# rpi-can-rs485.net
KiCad netlist of a schematic drawn in EAGLE
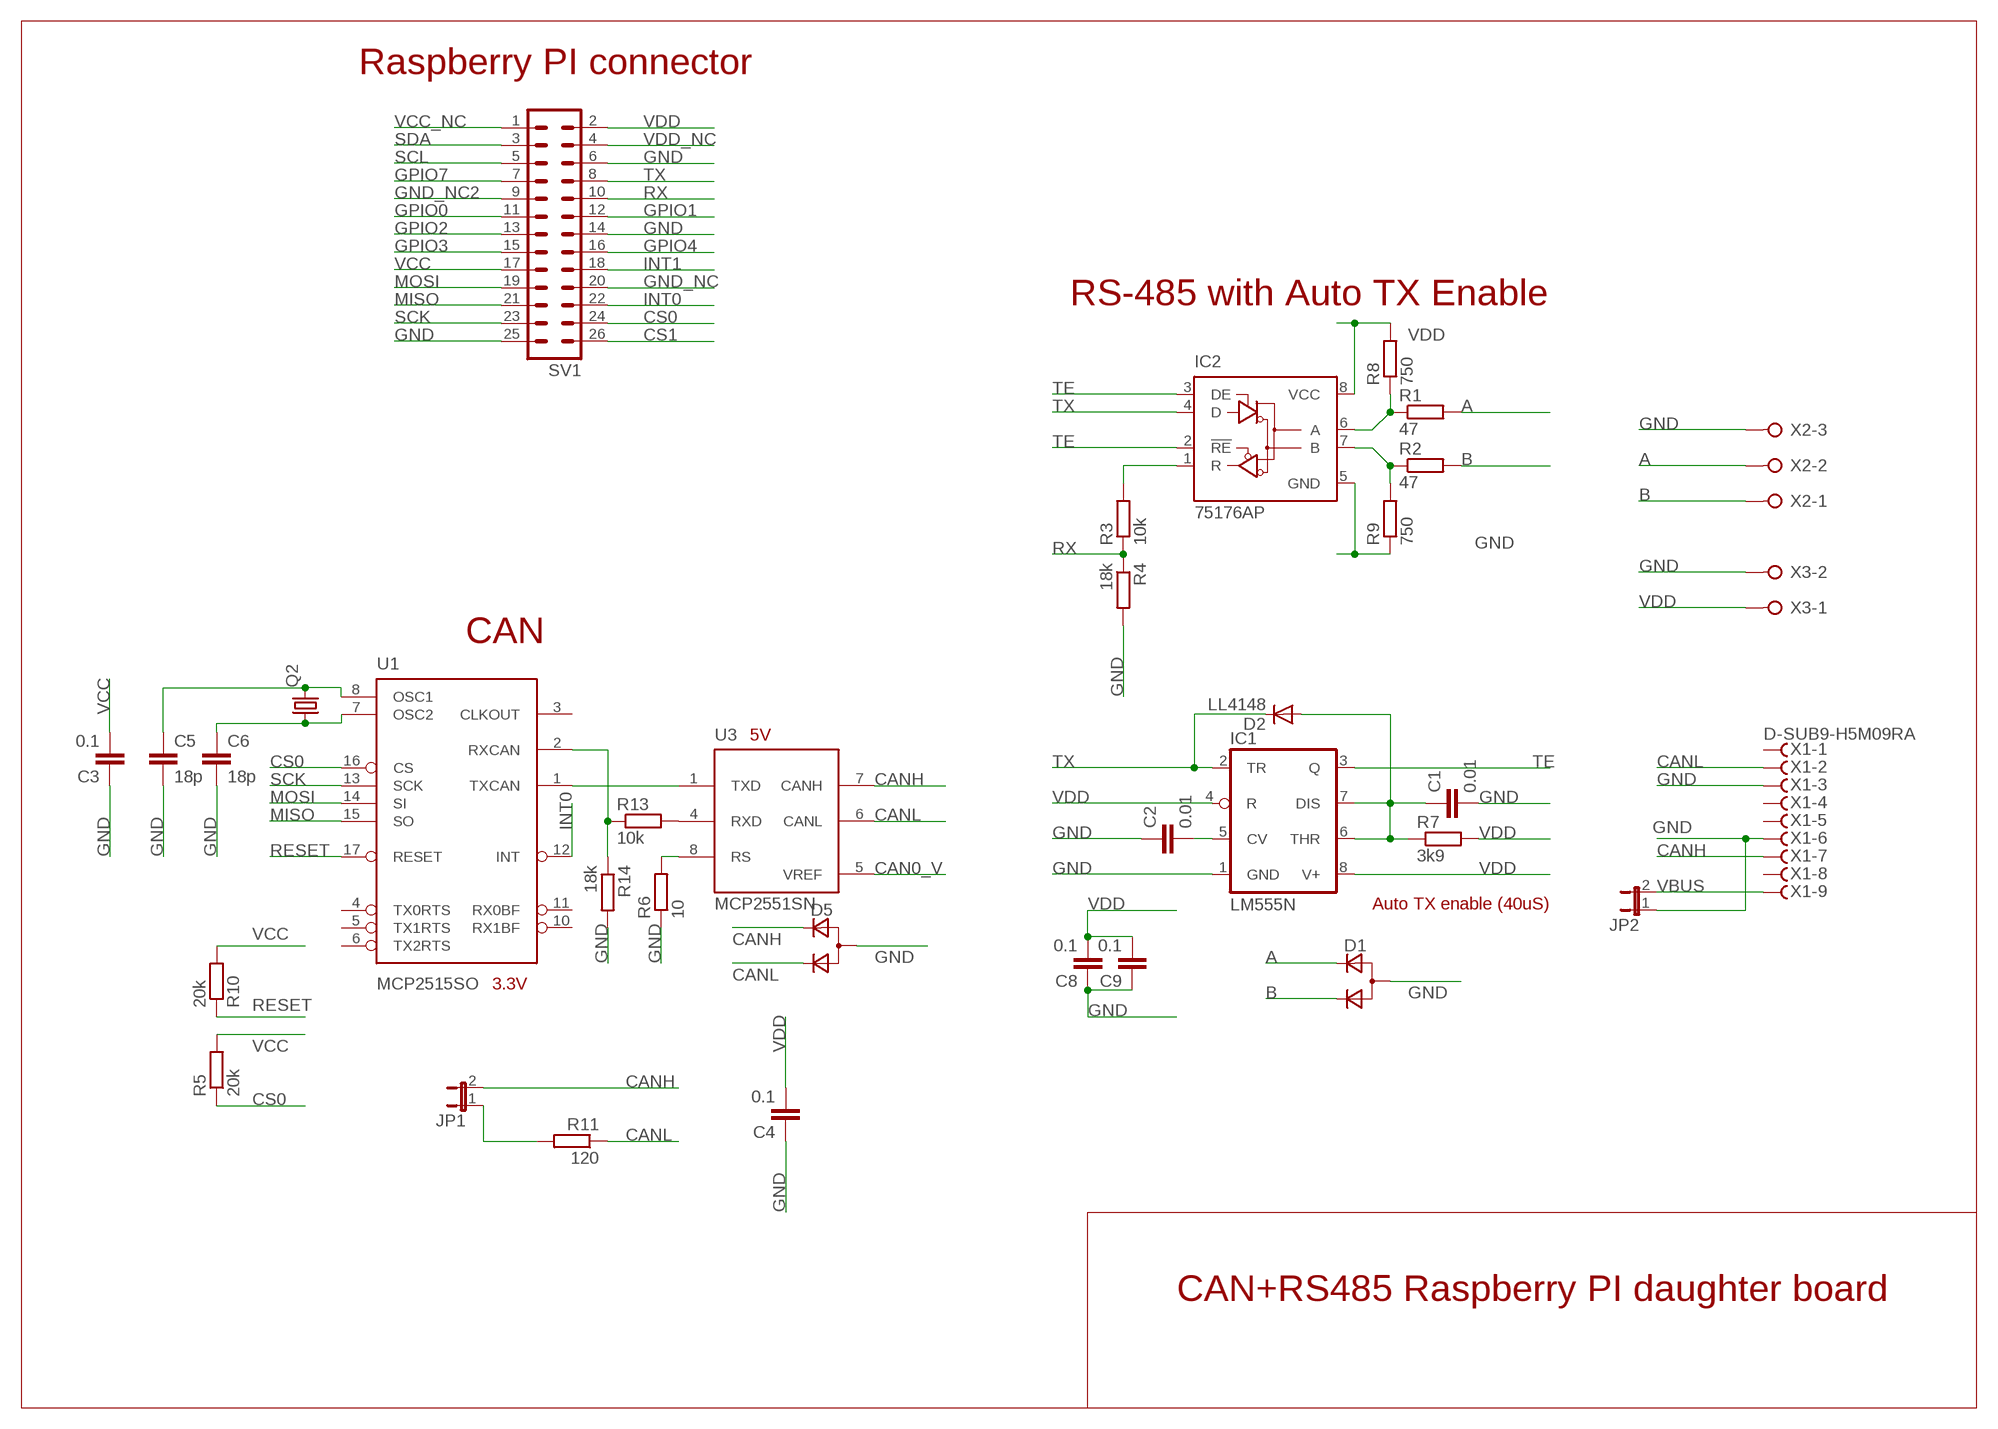
[diagram p0: schematic, sheet 1]

(export (version "E")
  (design (tool "Eeschema 10.0.6"))
  (components
    (comp (ref "C1")
      (value "0.01")
      (footprint "eagle-import:C0805")
      (libsource (lib "eagle-import") (part "C-EUC0805"))
    )
    (comp (ref "C2")
      (value "0.01")
      (footprint "eagle-import:C0805")
      (libsource (lib "eagle-import") (part "C-EUC0805"))
    )
    (comp (ref "C3")
      (value "0.1")
      (footprint "eagle-import:C0805")
      (libsource (lib "eagle-import") (part "C-EUC0805"))
    )
    (comp (ref "C4")
      (value "0.1")
      (footprint "eagle-import:C0805")
      (libsource (lib "eagle-import") (part "C-EUC0805"))
    )
    (comp (ref "C5")
      (value "18p")
      (footprint "eagle-import:C0805")
      (libsource (lib "eagle-import") (part "C-EUC0805"))
    )
    (comp (ref "C6")
      (value "18p")
      (footprint "eagle-import:C0805")
      (libsource (lib "eagle-import") (part "C-EUC0805"))
    )
    (comp (ref "C8")
      (value "0.1")
      (footprint "eagle-import:C0805")
      (libsource (lib "eagle-import") (part "C-EUC0805"))
    )
    (comp (ref "C9")
      (value "0.1")
      (footprint "eagle-import:C0805")
      (libsource (lib "eagle-import") (part "C-EUC0805"))
    )
    (comp (ref "D1")
      (value "D_2CSOT323")
      (footprint "eagle-import:SOT323")
      (libsource (lib "eagle-import") (part "D_2CSOT323"))
    )
    (comp (ref "D2")
      (value "LL4148")
      (footprint "eagle-import:SOD80C")
      (libsource (lib "eagle-import") (part "DIODE-SOD80C"))
    )
    (comp (ref "D5")
      (value "D_2CSOT323")
      (footprint "eagle-import:SOT323")
      (libsource (lib "eagle-import") (part "D_2CSOT323"))
    )
    (comp (ref "IC1")
      (value "LM555N")
      (footprint "eagle-import:DIL08")
      (libsource (lib "eagle-import") (part "555NLM"))
    )
    (comp (ref "IC2")
      (value "75176AP")
      (footprint "eagle-import:DIL08")
      (libsource (lib "eagle-import") (part "75176AP"))
    )
    (comp (ref "JP1")
      (value "JP1E")
      (footprint "eagle-import:JP1")
      (libsource (lib "eagle-import") (part "JP1E"))
    )
    (comp (ref "JP2")
      (value "JP1E")
      (footprint "eagle-import:JP1")
      (libsource (lib "eagle-import") (part "JP1E"))
    )
    (comp (ref "Q2")
      (value "CRYSTALHC49S")
      (footprint "eagle-import:HC49_S")
      (libsource (lib "eagle-import") (part "CRYSTALHC49S"))
    )
    (comp (ref "R1")
      (value "47")
      (footprint "eagle-import:R1206")
      (libsource (lib "eagle-import") (part "R-EU_R1206"))
    )
    (comp (ref "R2")
      (value "47")
      (footprint "eagle-import:R1206")
      (libsource (lib "eagle-import") (part "R-EU_R1206"))
    )
    (comp (ref "R3")
      (value "10k")
      (footprint "eagle-import:R0805")
      (libsource (lib "eagle-import") (part "R-EU_R0805"))
    )
    (comp (ref "R4")
      (value "18k")
      (footprint "eagle-import:R0805")
      (libsource (lib "eagle-import") (part "R-EU_R0805"))
    )
    (comp (ref "R5")
      (value "20k")
      (footprint "eagle-import:R0603")
      (libsource (lib "eagle-import") (part "R-EU_R0603"))
    )
    (comp (ref "R6")
      (value "10")
      (footprint "eagle-import:R0805")
      (libsource (lib "eagle-import") (part "R-EU_R0805"))
    )
    (comp (ref "R7")
      (value "3k9")
      (footprint "eagle-import:R0805")
      (libsource (lib "eagle-import") (part "R-EU_R0805"))
    )
    (comp (ref "R8")
      (value "750")
      (footprint "eagle-import:R1206")
      (libsource (lib "eagle-import") (part "R-EU_R1206"))
    )
    (comp (ref "R9")
      (value "750")
      (footprint "eagle-import:R1206")
      (libsource (lib "eagle-import") (part "R-EU_R1206"))
    )
    (comp (ref "R10")
      (value "20k")
      (footprint "eagle-import:R0805")
      (libsource (lib "eagle-import") (part "R-EU_R0805"))
    )
    (comp (ref "R11")
      (value "120")
      (footprint "eagle-import:R0805")
      (libsource (lib "eagle-import") (part "R-EU_R0805"))
    )
    (comp (ref "R13")
      (value "10k")
      (footprint "eagle-import:R0805")
      (libsource (lib "eagle-import") (part "R-EU_R0805"))
    )
    (comp (ref "R14")
      (value "18k")
      (footprint "eagle-import:R0805")
      (libsource (lib "eagle-import") (part "R-EU_R0805"))
    )
    (comp (ref "SV1")
      (value "MA13-2")
      (footprint "eagle-import:MA13-2")
      (libsource (lib "eagle-import") (part "MA13-2"))
    )
    (comp (ref "U1")
      (value "MCP2515SO")
      (footprint "eagle-import:SO-18W")
      (libsource (lib "eagle-import") (part "MCP2510SO"))
    )
    (comp (ref "U3")
      (value "MCP2551SN")
      (footprint "eagle-import:SO-08")
      (libsource (lib "eagle-import") (part "MCP2551SN"))
    )
    (comp (ref "X1")
      (value "D-SUB9-H5M09RA")
      (footprint "eagle-import:H5M09RA")
      (libsource (lib "eagle-import") (part "D-SUB9-H5M09RA"))
    )
    (comp (ref "X2")
      (value "W237-03P")
      (footprint "eagle-import:W237-133")
      (libsource (lib "eagle-import") (part "W237-03P"))
    )
    (comp (ref "X3")
      (value "W237-02P")
      (footprint "eagle-import:W237-132")
      (libsource (lib "eagle-import") (part "W237-02P"))
    )
  )
  (nets
    (net (code "1") (name "/A") (class "Default")
      (node (ref "D1") (pin "2") (pinfunction "C1_2") (pintype "passive"))
      (node (ref "R1") (pin "2") (pinfunction "2_2") (pintype "passive"))
      (node (ref "X2") (pin "2") (pinfunction "KL_2") (pintype "passive"))
    )
    (net (code "2") (name "/B") (class "Default")
      (node (ref "D1") (pin "3") (pinfunction "C2_3") (pintype "passive"))
      (node (ref "R2") (pin "2") (pinfunction "2_2") (pintype "passive"))
      (node (ref "X2") (pin "1") (pinfunction "KL_1") (pintype "passive"))
    )
    (net (code "3") (name "/CAN0_V") (class "Default")
      (node (ref "U3") (pin "5") (pinfunction "VREF_5") (pintype "power_in"))
    )
    (net (code "4") (name "/CANH") (class "Default")
      (node (ref "D5") (pin "2") (pinfunction "C1_2") (pintype "passive"))
      (node (ref "JP1") (pin "2") (pinfunction "2_2") (pintype "passive"))
      (node (ref "U3") (pin "7") (pinfunction "CANH_7") (pintype "bidirectional"))
      (node (ref "X1") (pin "7") (pinfunction "F_7") (pintype "passive"))
    )
    (net (code "5") (name "/CANL") (class "Default")
      (node (ref "D5") (pin "3") (pinfunction "C2_3") (pintype "passive"))
      (node (ref "R11") (pin "1") (pinfunction "1_1") (pintype "passive"))
      (node (ref "U3") (pin "6") (pinfunction "CANL_6") (pintype "bidirectional"))
      (node (ref "X1") (pin "2") (pinfunction "F_2") (pintype "passive"))
    )
    (net (code "6") (name "/CS0") (class "Default")
      (node (ref "R5") (pin "1") (pinfunction "1_1") (pintype "passive"))
      (node (ref "SV1") (pin "24") (pinfunction "24_24") (pintype "passive"))
      (node (ref "U1") (pin "16") (pinfunction "CS_16") (pintype "input"))
    )
    (net (code "7") (name "/CS1") (class "Default")
      (node (ref "SV1") (pin "26") (pinfunction "26_26") (pintype "passive"))
    )
    (net (code "8") (name "/GND") (class "Default")
      (node (ref "C1") (pin "2") (pinfunction "2_2") (pintype "passive"))
      (node (ref "C2") (pin "1") (pinfunction "1_1") (pintype "passive"))
      (node (ref "C3") (pin "1") (pinfunction "1_1") (pintype "passive"))
      (node (ref "C4") (pin "1") (pinfunction "1_1") (pintype "passive"))
      (node (ref "C5") (pin "2") (pinfunction "2_2") (pintype "passive"))
      (node (ref "C6") (pin "2") (pinfunction "2_2") (pintype "passive"))
      (node (ref "C8") (pin "1") (pinfunction "1_1") (pintype "passive"))
      (node (ref "C9") (pin "1") (pinfunction "1_1") (pintype "passive"))
      (node (ref "D1") (pin "1") (pinfunction "A_1") (pintype "passive"))
      (node (ref "D5") (pin "1") (pinfunction "A_1") (pintype "passive"))
      (node (ref "IC1") (pin "1") (pinfunction "GND_1") (pintype "power_in"))
      (node (ref "IC2") (pin "5") (pinfunction "GND_5") (pintype "power_in"))
      (node (ref "JP2") (pin "1") (pinfunction "1_1") (pintype "passive"))
      (node (ref "R14") (pin "2") (pinfunction "2_2") (pintype "passive"))
      (node (ref "R4") (pin "2") (pinfunction "2_2") (pintype "passive"))
      (node (ref "R6") (pin "1") (pinfunction "1_1") (pintype "passive"))
      (node (ref "R9") (pin "1") (pinfunction "1_1") (pintype "passive"))
      (node (ref "SV1") (pin "14") (pinfunction "14_14") (pintype "passive"))
      (node (ref "SV1") (pin "25") (pinfunction "25_25") (pintype "passive"))
      (node (ref "SV1") (pin "6") (pinfunction "6_6") (pintype "passive"))
      (node (ref "X1") (pin "3") (pinfunction "F_3") (pintype "passive"))
      (node (ref "X1") (pin "6") (pinfunction "F_6") (pintype "passive"))
      (node (ref "X2") (pin "3") (pinfunction "KL_3") (pintype "passive"))
      (node (ref "X3") (pin "2") (pinfunction "KL_2") (pintype "passive"))
    )
    (net (code "9") (name "/GND_NC") (class "Default")
      (node (ref "SV1") (pin "20") (pinfunction "20_20") (pintype "passive"))
    )
    (net (code "10") (name "/GND_NC2") (class "Default")
      (node (ref "SV1") (pin "9") (pinfunction "9_9") (pintype "passive"))
    )
    (net (code "11") (name "/GPIO0") (class "Default")
      (node (ref "SV1") (pin "11") (pinfunction "11_11") (pintype "passive"))
    )
    (net (code "12") (name "/GPIO1") (class "Default")
      (node (ref "SV1") (pin "12") (pinfunction "12_12") (pintype "passive"))
    )
    (net (code "13") (name "/GPIO2") (class "Default")
      (node (ref "SV1") (pin "13") (pinfunction "13_13") (pintype "passive"))
    )
    (net (code "14") (name "/GPIO3") (class "Default")
      (node (ref "SV1") (pin "15") (pinfunction "15_15") (pintype "passive"))
    )
    (net (code "15") (name "/GPIO4") (class "Default")
      (node (ref "SV1") (pin "16") (pinfunction "16_16") (pintype "passive"))
    )
    (net (code "16") (name "/GPIO7") (class "Default")
      (node (ref "SV1") (pin "7") (pinfunction "7_7") (pintype "passive"))
    )
    (net (code "17") (name "/INT0") (class "Default")
      (node (ref "SV1") (pin "22") (pinfunction "22_22") (pintype "passive"))
      (node (ref "U1") (pin "12") (pinfunction "INT_12") (pintype "output"))
    )
    (net (code "18") (name "/INT1") (class "Default")
      (node (ref "SV1") (pin "18") (pinfunction "18_18") (pintype "passive"))
    )
    (net (code "19") (name "/MISO") (class "Default")
      (node (ref "SV1") (pin "21") (pinfunction "21_21") (pintype "passive"))
      (node (ref "U1") (pin "15") (pinfunction "SO_15") (pintype "output"))
    )
    (net (code "20") (name "/MOSI") (class "Default")
      (node (ref "SV1") (pin "19") (pinfunction "19_19") (pintype "passive"))
      (node (ref "U1") (pin "14") (pinfunction "SI_14") (pintype "input"))
    )
    (net (code "21") (name "/RESET") (class "Default")
      (node (ref "R10") (pin "1") (pinfunction "1_1") (pintype "passive"))
      (node (ref "U1") (pin "17") (pinfunction "RESET_17") (pintype "input"))
    )
    (net (code "22") (name "/RX") (class "Default")
      (node (ref "R3") (pin "1") (pinfunction "1_1") (pintype "passive"))
      (node (ref "R4") (pin "1") (pinfunction "1_1") (pintype "passive"))
      (node (ref "SV1") (pin "10") (pinfunction "10_10") (pintype "passive"))
    )
    (net (code "23") (name "/SCK") (class "Default")
      (node (ref "SV1") (pin "23") (pinfunction "23_23") (pintype "passive"))
      (node (ref "U1") (pin "13") (pinfunction "SCK_13") (pintype "input"))
    )
    (net (code "24") (name "/SCL") (class "Default")
      (node (ref "SV1") (pin "5") (pinfunction "5_5") (pintype "passive"))
    )
    (net (code "25") (name "/SDA") (class "Default")
      (node (ref "SV1") (pin "3") (pinfunction "3_3") (pintype "passive"))
    )
    (net (code "26") (name "/TE") (class "Default")
      (node (ref "IC1") (pin "3") (pinfunction "Q_3") (pintype "output"))
      (node (ref "IC2") (pin "2") (pinfunction "~{RE}_2") (pintype "input"))
      (node (ref "IC2") (pin "3") (pinfunction "DE_3") (pintype "input"))
    )
    (net (code "27") (name "/TX") (class "Default")
      (node (ref "D2") (pin "C") (pinfunction "C_C") (pintype "passive"))
      (node (ref "IC1") (pin "2") (pinfunction "TR_2") (pintype "input"))
      (node (ref "IC2") (pin "4") (pinfunction "D_4") (pintype "input"))
      (node (ref "SV1") (pin "8") (pinfunction "8_8") (pintype "passive"))
    )
    (net (code "28") (name "/VBUS") (class "Default")
      (node (ref "JP2") (pin "2") (pinfunction "2_2") (pintype "passive"))
      (node (ref "X1") (pin "9") (pinfunction "F_9") (pintype "passive"))
    )
    (net (code "29") (name "/VCC") (class "Default")
      (node (ref "C3") (pin "2") (pinfunction "2_2") (pintype "passive"))
      (node (ref "R10") (pin "2") (pinfunction "2_2") (pintype "passive"))
      (node (ref "R5") (pin "2") (pinfunction "2_2") (pintype "passive"))
      (node (ref "SV1") (pin "17") (pinfunction "17_17") (pintype "passive"))
    )
    (net (code "30") (name "/VCC_NC") (class "Default")
      (node (ref "SV1") (pin "1") (pinfunction "1_1") (pintype "passive"))
    )
    (net (code "31") (name "/VDD") (class "Default")
      (node (ref "C4") (pin "2") (pinfunction "2_2") (pintype "passive"))
      (node (ref "C8") (pin "2") (pinfunction "2_2") (pintype "passive"))
      (node (ref "C9") (pin "2") (pinfunction "2_2") (pintype "passive"))
      (node (ref "IC1") (pin "4") (pinfunction "R_4") (pintype "input"))
      (node (ref "IC1") (pin "8") (pinfunction "V+_8") (pintype "power_in"))
      (node (ref "IC2") (pin "8") (pinfunction "VCC_8") (pintype "power_in"))
      (node (ref "R7") (pin "2") (pinfunction "2_2") (pintype "passive"))
      (node (ref "R8") (pin "2") (pinfunction "2_2") (pintype "passive"))
      (node (ref "SV1") (pin "2") (pinfunction "2_2") (pintype "passive"))
      (node (ref "X3") (pin "1") (pinfunction "KL_1") (pintype "passive"))
    )
    (net (code "32") (name "/VDD_NC") (class "Default")
      (node (ref "SV1") (pin "4") (pinfunction "4_4") (pintype "passive"))
    )
    (net (code "33") (name "Net-(IC1-CV)") (class "Default")
      (node (ref "C2") (pin "2") (pinfunction "2_2") (pintype "passive"))
      (node (ref "IC1") (pin "5") (pinfunction "CV_5") (pintype "input"))
    )
    (net (code "34") (name "Net-(IC1-DIS)") (class "Default")
      (node (ref "C1") (pin "1") (pinfunction "1_1") (pintype "passive"))
      (node (ref "D2") (pin "A") (pinfunction "A_A") (pintype "passive"))
      (node (ref "IC1") (pin "6") (pinfunction "THR_6") (pintype "input"))
      (node (ref "IC1") (pin "7") (pinfunction "DIS_7") (pintype "input"))
      (node (ref "R7") (pin "1") (pinfunction "1_1") (pintype "passive"))
    )
    (net (code "35") (name "Net-(IC2-A)") (class "Default")
      (node (ref "IC2") (pin "6") (pinfunction "A_6") (pintype "output"))
      (node (ref "R1") (pin "1") (pinfunction "1_1") (pintype "passive"))
      (node (ref "R8") (pin "1") (pinfunction "1_1") (pintype "passive"))
    )
    (net (code "36") (name "Net-(IC2-B)") (class "Default")
      (node (ref "IC2") (pin "7") (pinfunction "B_7") (pintype "output"))
      (node (ref "R2") (pin "1") (pinfunction "1_1") (pintype "passive"))
      (node (ref "R9") (pin "2") (pinfunction "2_2") (pintype "passive"))
    )
    (net (code "37") (name "Net-(IC2-R)") (class "Default")
      (node (ref "IC2") (pin "1") (pinfunction "R_1") (pintype "input"))
      (node (ref "R3") (pin "2") (pinfunction "2_2") (pintype "passive"))
    )
    (net (code "38") (name "Net-(JP1-Pad1)") (class "Default")
      (node (ref "JP1") (pin "1") (pinfunction "1_1") (pintype "passive"))
      (node (ref "R11") (pin "2") (pinfunction "2_2") (pintype "passive"))
    )
    (net (code "39") (name "Net-(U1A-OSC1)") (class "Default")
      (node (ref "C5") (pin "1") (pinfunction "1_1") (pintype "passive"))
      (node (ref "Q2") (pin "2") (pinfunction "2_2") (pintype "passive"))
      (node (ref "U1") (pin "8") (pinfunction "OSC1_8") (pintype "input"))
    )
    (net (code "40") (name "Net-(U1A-OSC2)") (class "Default")
      (node (ref "C6") (pin "1") (pinfunction "1_1") (pintype "passive"))
      (node (ref "Q2") (pin "1") (pinfunction "1_1") (pintype "passive"))
      (node (ref "U1") (pin "7") (pinfunction "OSC2_7") (pintype "output"))
    )
    (net (code "41") (name "Net-(U1A-RXCAN)") (class "Default")
      (node (ref "R13") (pin "1") (pinfunction "1_1") (pintype "passive"))
      (node (ref "R14") (pin "1") (pinfunction "1_1") (pintype "passive"))
      (node (ref "U1") (pin "2") (pinfunction "RXCAN_2") (pintype "input"))
    )
    (net (code "42") (name "Net-(U1A-TXCAN)") (class "Default")
      (node (ref "U1") (pin "1") (pinfunction "TXCAN_1") (pintype "output"))
      (node (ref "U3") (pin "1") (pinfunction "TXD_1") (pintype "input"))
    )
    (net (code "43") (name "Net-(U3A-RS)") (class "Default")
      (node (ref "R6") (pin "2") (pinfunction "2_2") (pintype "passive"))
      (node (ref "U3") (pin "8") (pinfunction "RS_8") (pintype "input"))
    )
    (net (code "44") (name "Net-(U3A-RXD)") (class "Default")
      (node (ref "R13") (pin "2") (pinfunction "2_2") (pintype "passive"))
      (node (ref "U3") (pin "4") (pinfunction "RXD_4") (pintype "output"))
    )
    (net (code "45") (name "unconnected-(U1A-CLKOUT-Pad3)") (class "Default")
      (node (ref "U1") (pin "3") (pinfunction "CLKOUT_3") (pintype "output"))
    )
    (net (code "46") (name "unconnected-(U1A-RX0BF-Pad11)") (class "Default")
      (node (ref "U1") (pin "11") (pinfunction "RX0BF_11") (pintype "output"))
    )
    (net (code "47") (name "unconnected-(U1A-RX1BF-Pad10)") (class "Default")
      (node (ref "U1") (pin "10") (pinfunction "RX1BF_10") (pintype "output"))
    )
    (net (code "48") (name "unconnected-(U1A-TX0RTS-Pad4)") (class "Default")
      (node (ref "U1") (pin "4") (pinfunction "TX0RTS_4") (pintype "input"))
    )
    (net (code "49") (name "unconnected-(U1A-TX1RTS-Pad5)") (class "Default")
      (node (ref "U1") (pin "5") (pinfunction "TX1RTS_5") (pintype "input"))
    )
    (net (code "50") (name "unconnected-(U1A-TX2RTS-Pad6)") (class "Default")
      (node (ref "U1") (pin "6") (pinfunction "TX2RTS_6") (pintype "input"))
    )
    (net (code "51") (name "unconnected-(X1A-F-Pad1)") (class "Default")
      (node (ref "X1") (pin "1") (pinfunction "F_1") (pintype "passive"))
    )
    (net (code "52") (name "unconnected-(X1D-F-Pad4)") (class "Default")
      (node (ref "X1") (pin "4") (pinfunction "F_4") (pintype "passive"))
    )
    (net (code "53") (name "unconnected-(X1E-F-Pad5)") (class "Default")
      (node (ref "X1") (pin "5") (pinfunction "F_5") (pintype "passive"))
    )
    (net (code "54") (name "unconnected-(X1H-F-Pad8)") (class "Default")
      (node (ref "X1") (pin "8") (pinfunction "F_8") (pintype "passive"))
    )
  )
)
